# 2026.net
KiCad netlist of a schematic drawn in EasyEDA
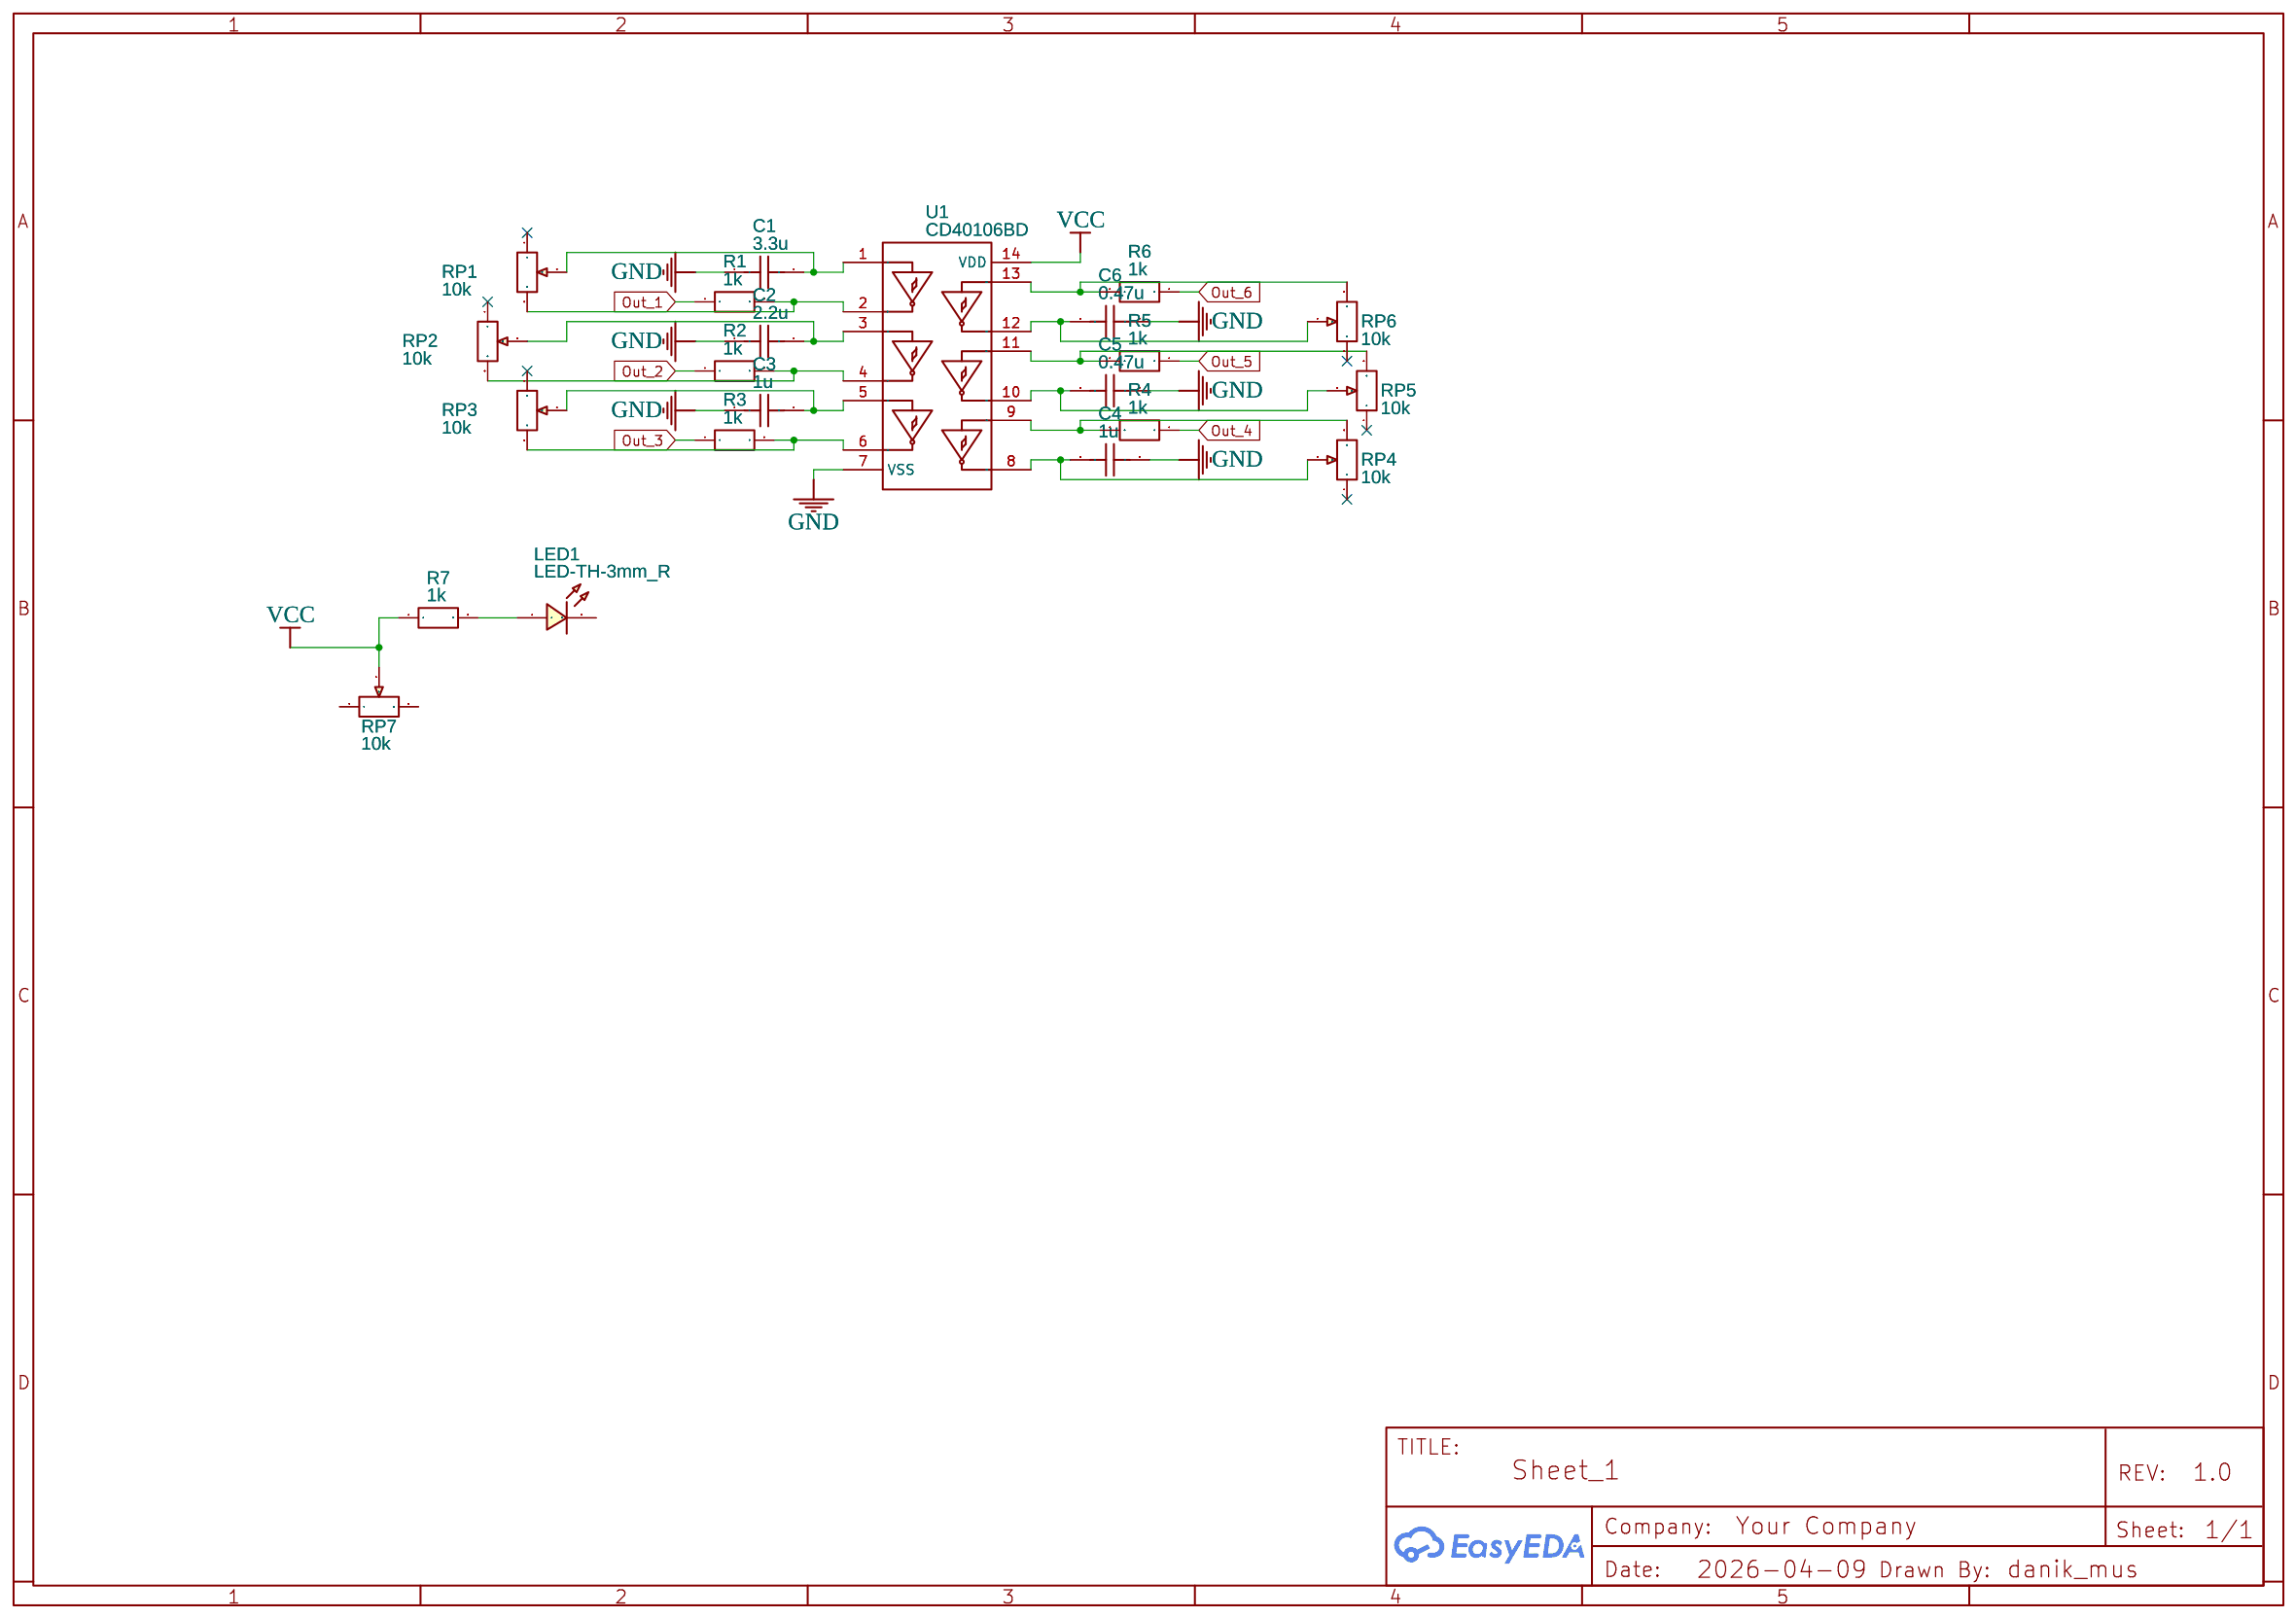
[diagram p0: schematic sheet]

(export (version "E")
  (design (tool "Eeschema 10.0.6"))
  (components
    (comp (ref "C1") (value "3.3u") (libsource (lib "") (part "C_0603_US_1")))
    (comp (ref "C2") (value "2.2u") (libsource (lib "") (part "C_0603_US_1")))
    (comp (ref "C3") (value "1u") (libsource (lib "") (part "C_0603_US_1")))
    (comp (ref "C4") (value "1u") (libsource (lib "") (part "C_0603_US")))
    (comp (ref "C5") (value "0.47u") (libsource (lib "") (part "C_0603_US")))
    (comp (ref "C6") (value "0.47u") (libsource (lib "") (part "C_0603_US")))
    (comp (ref "LED1")
      (value "LED-TH-3mm_R")
      (fields
        (field (name "Manufacturer Part") "204-10SDRD/S530-A3-L")
        (field (name "Manufacturer") "EVERLIGHT(台湾亿光)")
      )
      (libsource (lib "") (part "LED-TH-3mm_R"))
    )
    (comp (ref "R1") (value "1k") (libsource (lib "") (part "R_AXIAL-1.0_EU_1")))
    (comp (ref "R2") (value "1k") (libsource (lib "") (part "R_AXIAL-1.0_EU_1")))
    (comp (ref "R3") (value "1k") (libsource (lib "") (part "R_AXIAL-1.0_EU_1")))
    (comp (ref "R4") (value "1k") (libsource (lib "") (part "R_AXIAL-1.0_EU")))
    (comp (ref "R5") (value "1k") (libsource (lib "") (part "R_AXIAL-1.0_EU")))
    (comp (ref "R6") (value "1k") (libsource (lib "") (part "R_AXIAL-1.0_EU")))
    (comp (ref "R7") (value "1k") (libsource (lib "") (part "R_AXIAL-1.0_EU_1")))
    (comp (ref "RP1") (value "10k") (libsource (lib "") (part "POTRES COPY COPY_2")))
    (comp (ref "RP2") (value "10k") (libsource (lib "") (part "POTRES COPY COPY_2")))
    (comp (ref "RP3") (value "10k") (libsource (lib "") (part "POTRES COPY COPY_2")))
    (comp (ref "RP4") (value "10k") (libsource (lib "") (part "POTRES COPY COPY")))
    (comp (ref "RP5") (value "10k") (libsource (lib "") (part "POTRES COPY COPY")))
    (comp (ref "RP6") (value "10k") (libsource (lib "") (part "POTRES COPY COPY")))
    (comp (ref "RP7") (value "10k") (libsource (lib "") (part "POTRES COPY COPY_1")))
    (comp (ref "U1")
      (value "CD40106BD")
      (fields (field (name "Manufacturer") "Sungine(双竞集成)"))
      (libsource (lib "") (part "CD40106BD"))
    )
  )
  (nets
    (net (code "1") (name "GND") (class "Default")
      (node (ref "C1") (pin "1") (pinfunction "1_1") (pintype "unspecified"))
      (node (ref "C2") (pin "1") (pinfunction "1_1") (pintype "unspecified"))
      (node (ref "C3") (pin "1") (pinfunction "1_1") (pintype "unspecified"))
      (node (ref "C4") (pin "1") (pinfunction "1_1") (pintype "unspecified"))
      (node (ref "C5") (pin "1") (pinfunction "1_1") (pintype "unspecified"))
      (node (ref "C6") (pin "1") (pinfunction "1_1") (pintype "unspecified"))
      (node (ref "U1") (pin "7") (pinfunction "VSS_7") (pintype "unspecified"))
    )
    (net (code "2") (name "Net-(C1-Pad2)") (class "Default")
      (node (ref "C1") (pin "2") (pinfunction "2_2") (pintype "unspecified"))
      (node (ref "RP1") (pin "2") (pinfunction "2_2") (pintype "input"))
      (node (ref "U1") (pin "1") (pinfunction "1_1") (pintype "unspecified"))
    )
    (net (code "3") (name "Net-(C2-Pad2)") (class "Default")
      (node (ref "C2") (pin "2") (pinfunction "2_2") (pintype "unspecified"))
      (node (ref "RP2") (pin "2") (pinfunction "2_2") (pintype "input"))
      (node (ref "U1") (pin "3") (pinfunction "3_3") (pintype "unspecified"))
    )
    (net (code "4") (name "Net-(C3-Pad2)") (class "Default")
      (node (ref "C3") (pin "2") (pinfunction "2_2") (pintype "unspecified"))
      (node (ref "RP3") (pin "2") (pinfunction "2_2") (pintype "input"))
      (node (ref "U1") (pin "5") (pinfunction "5_5") (pintype "unspecified"))
    )
    (net (code "5") (name "Net-(C4-Pad2)") (class "Default")
      (node (ref "C4") (pin "2") (pinfunction "2_2") (pintype "unspecified"))
      (node (ref "RP4") (pin "2") (pinfunction "2_2") (pintype "input"))
      (node (ref "U1") (pin "8") (pinfunction "8_8") (pintype "unspecified"))
    )
    (net (code "6") (name "Net-(C5-Pad2)") (class "Default")
      (node (ref "C5") (pin "2") (pinfunction "2_2") (pintype "unspecified"))
      (node (ref "RP5") (pin "2") (pinfunction "2_2") (pintype "input"))
      (node (ref "U1") (pin "10") (pinfunction "10_10") (pintype "unspecified"))
    )
    (net (code "7") (name "Net-(C6-Pad2)") (class "Default")
      (node (ref "C6") (pin "2") (pinfunction "2_2") (pintype "unspecified"))
      (node (ref "RP6") (pin "2") (pinfunction "2_2") (pintype "input"))
      (node (ref "U1") (pin "12") (pinfunction "12_12") (pintype "unspecified"))
    )
    (net (code "8") (name "Net-(LED1-Pad1)") (class "Default")
      (node (ref "LED1") (pin "1") (pinfunction "1_1") (pintype "unspecified"))
      (node (ref "R7") (pin "2") (pinfunction "2_2") (pintype "unspecified"))
    )
    (net (code "9") (name "Net-(R1-Pad2)") (class "Default")
      (node (ref "R1") (pin "2") (pinfunction "2_2") (pintype "unspecified"))
      (node (ref "RP1") (pin "3") (pinfunction "3_3") (pintype "input"))
      (node (ref "U1") (pin "2") (pinfunction "2_2") (pintype "unspecified"))
    )
    (net (code "10") (name "Net-(R2-Pad2)") (class "Default")
      (node (ref "R2") (pin "2") (pinfunction "2_2") (pintype "unspecified"))
      (node (ref "RP2") (pin "3") (pinfunction "3_3") (pintype "input"))
      (node (ref "U1") (pin "4") (pinfunction "4_4") (pintype "unspecified"))
    )
    (net (code "11") (name "Net-(R3-Pad2)") (class "Default")
      (node (ref "R3") (pin "2") (pinfunction "2_2") (pintype "unspecified"))
      (node (ref "RP3") (pin "3") (pinfunction "3_3") (pintype "input"))
      (node (ref "U1") (pin "6") (pinfunction "6_6") (pintype "unspecified"))
    )
    (net (code "12") (name "Net-(R4-Pad2)") (class "Default")
      (node (ref "R4") (pin "2") (pinfunction "2_2") (pintype "unspecified"))
      (node (ref "RP4") (pin "3") (pinfunction "3_3") (pintype "input"))
      (node (ref "U1") (pin "9") (pinfunction "9_9") (pintype "unspecified"))
    )
    (net (code "13") (name "Net-(R5-Pad2)") (class "Default")
      (node (ref "R5") (pin "2") (pinfunction "2_2") (pintype "unspecified"))
      (node (ref "RP5") (pin "3") (pinfunction "3_3") (pintype "input"))
      (node (ref "U1") (pin "11") (pinfunction "11_11") (pintype "unspecified"))
    )
    (net (code "14") (name "Net-(R6-Pad2)") (class "Default")
      (node (ref "R6") (pin "2") (pinfunction "2_2") (pintype "unspecified"))
      (node (ref "RP6") (pin "3") (pinfunction "3_3") (pintype "input"))
      (node (ref "U1") (pin "13") (pinfunction "13_13") (pintype "unspecified"))
    )
    (net (code "15") (name "Out_1") (class "Default")
      (node (ref "R1") (pin "1") (pinfunction "1_1") (pintype "unspecified"))
    )
    (net (code "16") (name "Out_2") (class "Default")
      (node (ref "R2") (pin "1") (pinfunction "1_1") (pintype "unspecified"))
    )
    (net (code "17") (name "Out_3") (class "Default")
      (node (ref "R3") (pin "1") (pinfunction "1_1") (pintype "unspecified"))
    )
    (net (code "18") (name "Out_4") (class "Default")
      (node (ref "R4") (pin "1") (pinfunction "1_1") (pintype "unspecified"))
    )
    (net (code "19") (name "Out_5") (class "Default")
      (node (ref "R5") (pin "1") (pinfunction "1_1") (pintype "unspecified"))
    )
    (net (code "20") (name "Out_6") (class "Default")
      (node (ref "R6") (pin "1") (pinfunction "1_1") (pintype "unspecified"))
    )
    (net (code "21") (name "VCC") (class "Default")
      (node (ref "R7") (pin "1") (pinfunction "1_1") (pintype "unspecified"))
      (node (ref "RP7") (pin "2") (pinfunction "2_2") (pintype "input"))
      (node (ref "U1") (pin "14") (pinfunction "VDD_14") (pintype "unspecified"))
    )
    (net (code "22") (name "unconnected-(LED1-Pad2)") (class "Default")
      (node (ref "LED1") (pin "2") (pinfunction "2_2") (pintype "unspecified"))
    )
    (net (code "23") (name "unconnected-(RP1-Pad1)") (class "Default")
      (node (ref "RP1") (pin "1") (pinfunction "1_1") (pintype "input+no_connect"))
    )
    (net (code "24") (name "unconnected-(RP2-Pad1)") (class "Default")
      (node (ref "RP2") (pin "1") (pinfunction "1_1") (pintype "input+no_connect"))
    )
    (net (code "25") (name "unconnected-(RP3-Pad1)") (class "Default")
      (node (ref "RP3") (pin "1") (pinfunction "1_1") (pintype "input+no_connect"))
    )
    (net (code "26") (name "unconnected-(RP4-Pad1)") (class "Default")
      (node (ref "RP4") (pin "1") (pinfunction "1_1") (pintype "input+no_connect"))
    )
    (net (code "27") (name "unconnected-(RP5-Pad1)") (class "Default")
      (node (ref "RP5") (pin "1") (pinfunction "1_1") (pintype "input+no_connect"))
    )
    (net (code "28") (name "unconnected-(RP6-Pad1)") (class "Default")
      (node (ref "RP6") (pin "1") (pinfunction "1_1") (pintype "input+no_connect"))
    )
    (net (code "29") (name "unconnected-(RP7-Pad1)") (class "Default")
      (node (ref "RP7") (pin "1") (pinfunction "1_1") (pintype "input"))
    )
    (net (code "30") (name "unconnected-(RP7-Pad3)") (class "Default")
      (node (ref "RP7") (pin "3") (pinfunction "3_3") (pintype "input"))
    )
  )
)
